# Power.net
KiCad netlist of a schematic drawn in Altium Designer
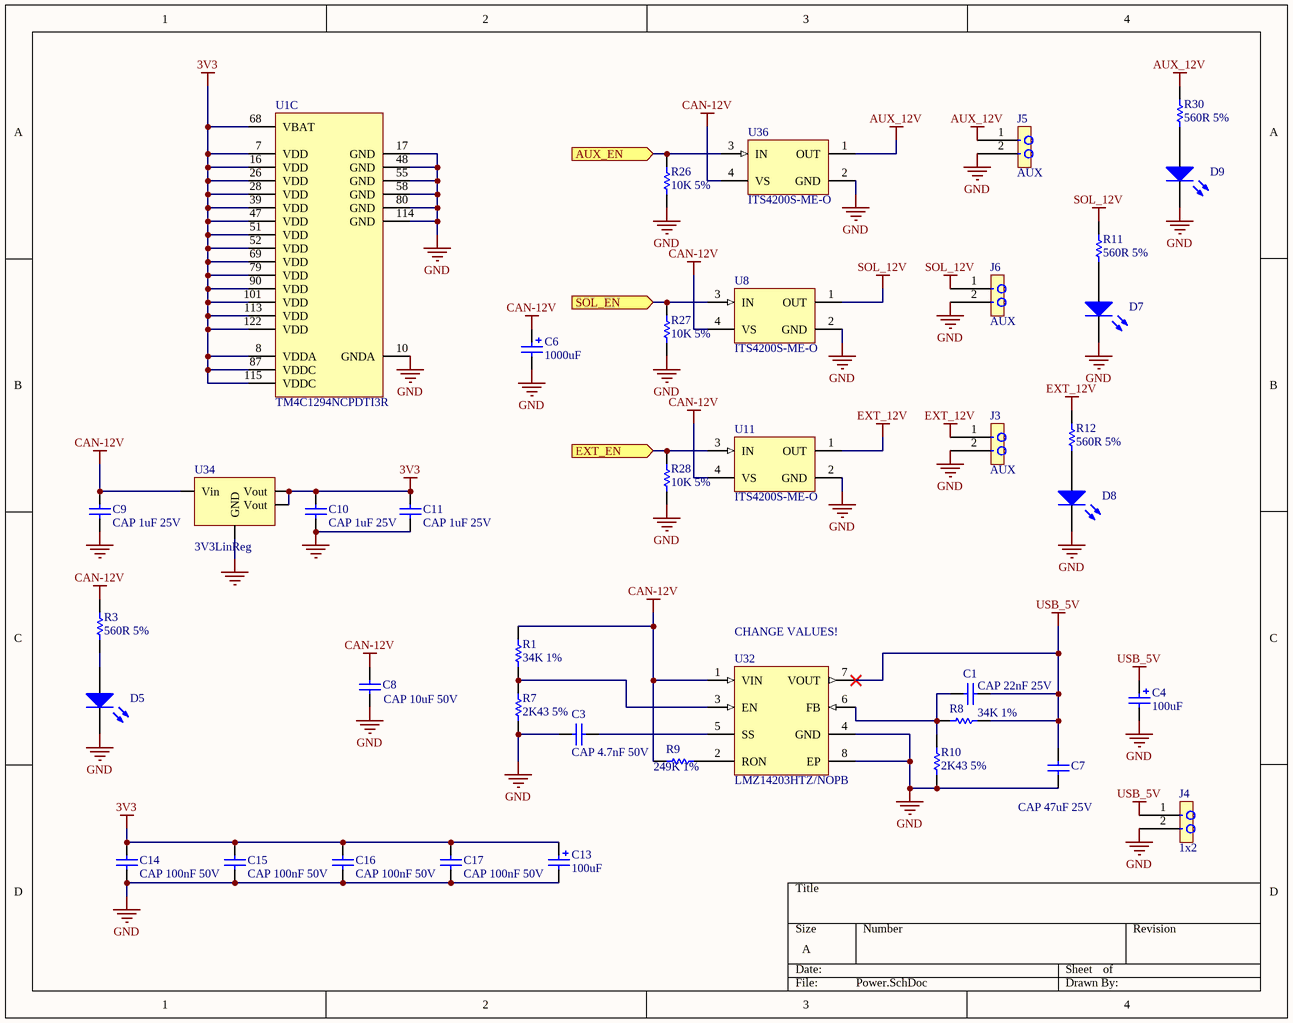
[diagram p0: Power.SchDoc]

(export (version "E")
  (design (tool "Eeschema 10.0.6"))
  (components
    (comp (ref "C1")
      (value "CAP 22nF 25V")
      (footprint "CAPC0805(2012)100_M")
      (description "CAP 22nF 25V Â±5% 0805 (2012 Metric) Thickness 1mm SMD")
      (fields (field (name "TOLERANCE") "Â±5%"))
      (libsource (lib "Altium Content Vault") (part "CMP-1036-04051-1"))
    )
    (comp (ref "C3")
      (value "CAP 4.7nF 50V")
      (footprint "CAPC0603(1608)100_M")
      (description "CAP 4.7nF 50V Â±20% 0603 (1608 Metric) Thickness 1mm SMD")
      (fields (field (name "TOLERANCE") "Â±20%"))
      (libsource (lib "Altium Content Vault") (part "CMP-1035-00333-1"))
    )
    (comp (ref "C4")
      (value "100uF")
      (footprint "PANASONIC_C")
      (description "Polarized Capacitor (Surface Mount)")
      (fields (field (name "PUBLISHER") "Altium Limited"))
      (libsource (lib "snarc+") (part "Cap_Polarized_100uF"))
    )
    (comp (ref "C6")
      (value "1000uF")
      (footprint "PANASONIC_H13")
      (description "Polarized Capacitor (Surface Mount)")
      (fields (field (name "PUBLISHER") "Altium Limited"))
      (libsource (lib "snarc+") (part "Cap_Polarized_1000uF"))
    )
    (comp (ref "C7")
      (value "CAP 47uF 25V")
      (footprint "CAPC1206(3216)100_L")
      (description "CAP 47uF 25V Â±0.25pF 1206 (3216 Metric) Thickness 1mm SMD")
      (fields (field (name "TOLERANCE") "Â±0.25pF"))
      (libsource (lib "Altium Content Vault") (part "CMP-1037-00376-1"))
    )
    (comp (ref "C8")
      (value "CAP 10uF 50V")
      (footprint "CAPC1206(3216)190_M")
      (description "CAP 10uF 50V Â±10% 1206 (3216 Metric) Thickness 1.9mm SMD")
      (fields (field (name "TOLERANCE") "Â±10%"))
      (libsource (lib "Altium Content Vault") (part "CMP-1037-04982-1"))
    )
    (comp (ref "C9")
      (value "CAP 1uF 25V")
      (footprint "CAPC0603(1608)100_M")
      (description "CAP 1uF 25V Â±0.25pF 0603 (1608 Metric) Thickness 1mm SMD")
      (fields (field (name "TOLERANCE") "Â±0.25pF"))
      (libsource (lib "Altium Content Vault") (part "CMP-1035-00037-1"))
    )
    (comp (ref "C10")
      (value "CAP 1uF 25V")
      (footprint "CAPC0603(1608)100_M")
      (description "CAP 1uF 25V Â±0.25pF 0603 (1608 Metric) Thickness 1mm SMD")
      (fields (field (name "TOLERANCE") "Â±0.25pF"))
      (libsource (lib "Altium Content Vault") (part "CMP-1035-00037-1"))
    )
    (comp (ref "C11")
      (value "CAP 1uF 25V")
      (footprint "CAPC0603(1608)100_M")
      (description "CAP 1uF 25V Â±0.25pF 0603 (1608 Metric) Thickness 1mm SMD")
      (fields (field (name "TOLERANCE") "Â±0.25pF"))
      (libsource (lib "Altium Content Vault") (part "CMP-1035-00037-1"))
    )
    (comp (ref "C13")
      (value "100uF")
      (footprint "PANASONIC_C")
      (description "Polarized Capacitor (Surface Mount)")
      (fields (field (name "PUBLISHER") "Altium Limited"))
      (libsource (lib "snarc+") (part "Cap_Polarized_100uF"))
    )
    (comp (ref "C14")
      (value "CAP 100nF 50V")
      (footprint "CAPC0603(1608)100_M")
      (description "CAP 100nF 50V Â±0.1pF 0603 (1608 Metric) Thickness 1mm SMD")
      (fields (field (name "TOLERANCE") "Â±0.1pF"))
      (libsource (lib "Altium Content Vault") (part "CMP-1035-00010-1"))
    )
    (comp (ref "C15")
      (value "CAP 100nF 50V")
      (footprint "CAPC0603(1608)100_M")
      (description "CAP 100nF 50V Â±0.1pF 0603 (1608 Metric) Thickness 1mm SMD")
      (fields (field (name "TOLERANCE") "Â±0.1pF"))
      (libsource (lib "Altium Content Vault") (part "CMP-1035-00010-1"))
    )
    (comp (ref "C16")
      (value "CAP 100nF 50V")
      (footprint "CAPC0603(1608)100_M")
      (description "CAP 100nF 50V Â±0.1pF 0603 (1608 Metric) Thickness 1mm SMD")
      (fields (field (name "TOLERANCE") "Â±0.1pF"))
      (libsource (lib "Altium Content Vault") (part "CMP-1035-00010-1"))
    )
    (comp (ref "C17")
      (value "CAP 100nF 50V")
      (footprint "CAPC0603(1608)100_M")
      (description "CAP 100nF 50V Â±0.1pF 0603 (1608 Metric) Thickness 1mm SMD")
      (fields (field (name "TOLERANCE") "Â±0.1pF"))
      (libsource (lib "Altium Content Vault") (part "CMP-1035-00010-1"))
    )
    (comp (ref "D5")
      (value "LED")
      (footprint "LED-0603")
      (description "Typical RED, GREEN, YELLOW, AMBER GaAs LED")
      (fields (field (name "PUBLISHER") "Altium Limited"))
      (libsource (lib "HSBNE-Vend") (part "LED"))
    )
    (comp (ref "D7")
      (value "LED")
      (footprint "LED-0603")
      (description "Typical RED, GREEN, YELLOW, AMBER GaAs LED")
      (fields (field (name "PUBLISHER") "Altium Limited"))
      (libsource (lib "HSBNE-Vend") (part "LED"))
    )
    (comp (ref "D8")
      (value "LED")
      (footprint "LED-0603")
      (description "Typical RED, GREEN, YELLOW, AMBER GaAs LED")
      (fields (field (name "PUBLISHER") "Altium Limited"))
      (libsource (lib "HSBNE-Vend") (part "LED"))
    )
    (comp (ref "D9")
      (value "LED")
      (footprint "LED-0603")
      (description "Typical RED, GREEN, YELLOW, AMBER GaAs LED")
      (fields (field (name "PUBLISHER") "Altium Limited"))
      (libsource (lib "HSBNE-Vend") (part "LED"))
    )
    (comp (ref "J3")
      (value "AUX")
      (footprint "M5569-2")
      (description "6.35mm right-angle 90° male spade terminal PCB mount")
      (libsource (lib "HSBNE-Vend") (part "CON2"))
    )
    (comp (ref "J4")
      (value "1x2")
      (footprint "1X2")
      (description "6.35mm right-angle 90° male spade terminal PCB mount")
      (libsource (lib "HSBNE-Vend") (part "CON2"))
    )
    (comp (ref "J5")
      (value "AUX")
      (footprint "M5569-2")
      (description "6.35mm right-angle 90° male spade terminal PCB mount")
      (libsource (lib "HSBNE-Vend") (part "CON2"))
    )
    (comp (ref "J6")
      (value "AUX")
      (footprint "M5569-2")
      (description "6.35mm right-angle 90° male spade terminal PCB mount")
      (libsource (lib "HSBNE-Vend") (part "CON2"))
    )
    (comp (ref "R1")
      (value "34K 1%")
      (footprint "RESC0603(1608)_M")
      (description "34K 0.1W 1% 0603 (1608 Metric)  SMD")
      (fields (field (name "TOLERANCE") "1 %") (field (name "POWER") "0.1 W"))
      (libsource (lib "Altium Content Vault") (part "CMP-1012-00682-1"))
    )
    (comp (ref "R3")
      (value "560R 5%")
      (footprint "RESC0603(1608)_M")
      (description "560R 0.1W 5% 0603 (1608 Metric)  SMD")
      (fields (field (name "TOLERANCE") "5 %") (field (name "POWER") "0.1 W"))
      (libsource (lib "Altium Content Vault") (part "RES"))
    )
    (comp (ref "R7")
      (value "2K43 5%")
      (footprint "RESC0603(1608)_M")
      (description "2K43 0.1W 5% 0603 (1608 Metric)  SMD")
      (fields (field (name "TOLERANCE") "5 %") (field (name "POWER") "0.1 W"))
      (libsource (lib "Altium Content Vault") (part "CMP-1012-00083-1"))
    )
    (comp (ref "R8")
      (value "34K 1%")
      (footprint "RESC0603(1608)_M")
      (description "34K 0.1W 1% 0603 (1608 Metric)  SMD")
      (fields (field (name "TOLERANCE") "1 %") (field (name "POWER") "0.1 W"))
      (libsource (lib "Altium Content Vault") (part "CMP-1012-00682-1"))
    )
    (comp (ref "R9")
      (value "249K 1%")
      (footprint "RESC0603(1608)_M")
      (description "249K 0.1W 1% 0603 (1608 Metric)  SMD")
      (fields (field (name "POWER") "0.1 W") (field (name "TOLERANCE") "1 %"))
      (libsource (lib "Altium Content Vault") (part "CMP-1012-00779-1"))
    )
    (comp (ref "R10")
      (value "2K43 5%")
      (footprint "RESC0603(1608)_M")
      (description "2K43 0.1W 5% 0603 (1608 Metric)  SMD")
      (fields (field (name "TOLERANCE") "5 %") (field (name "POWER") "0.1 W"))
      (libsource (lib "Altium Content Vault") (part "CMP-1012-00083-1"))
    )
    (comp (ref "R11")
      (value "560R 5%")
      (footprint "RESC0603(1608)_M")
      (description "560R 0.1W 5% 0603 (1608 Metric)  SMD")
      (fields (field (name "TOLERANCE") "5 %") (field (name "POWER") "0.1 W"))
      (libsource (lib "Altium Content Vault") (part "RES"))
    )
    (comp (ref "R12")
      (value "560R 5%")
      (footprint "RESC0603(1608)_M")
      (description "560R 0.1W 5% 0603 (1608 Metric)  SMD")
      (fields (field (name "TOLERANCE") "5 %") (field (name "POWER") "0.1 W"))
      (libsource (lib "Altium Content Vault") (part "RES"))
    )
    (comp (ref "R26")
      (value "10K 5%")
      (footprint "RESC0603(1608)_N")
      (description "10K 0.1W 5% 0603 (1608 Metric)  SMD")
      (fields (field (name "TOLERANCE") "5 %") (field (name "POWER") "0.1 W"))
      (libsource (lib "Altium Content Vault") (part "RES"))
    )
    (comp (ref "R27")
      (value "10K 5%")
      (footprint "RESC0603(1608)_N")
      (description "10K 0.1W 5% 0603 (1608 Metric)  SMD")
      (fields (field (name "TOLERANCE") "5 %") (field (name "POWER") "0.1 W"))
      (libsource (lib "Altium Content Vault") (part "RES"))
    )
    (comp (ref "R28")
      (value "10K 5%")
      (footprint "RESC0603(1608)_N")
      (description "10K 0.1W 5% 0603 (1608 Metric)  SMD")
      (fields (field (name "TOLERANCE") "5 %") (field (name "POWER") "0.1 W"))
      (libsource (lib "Altium Content Vault") (part "RES"))
    )
    (comp (ref "R30")
      (value "560R 5%")
      (footprint "RESC0603(1608)_M")
      (description "560R 0.1W 5% 0603 (1608 Metric)  SMD")
      (fields (field (name "TOLERANCE") "5 %") (field (name "POWER") "0.1 W"))
      (libsource (lib "Altium Content Vault") (part "RES"))
    )
    (comp (ref "U1")
      (value "TM4C1294NCPDTI3R")
      (footprint "TI-PDT128_M")
      (fields (field (name "MANUFACTURER") "Texas Instruments"))
      (libsource (lib "Altium Inc") (part "TI-TM4C1294NCPDT-128"))
    )
    (comp (ref "U8")
      (value "ITS4200S-ME-O")
      (footprint "INF-SOT223_M")
      (description "Smart High-Side NMOS-Power Switch, 11 to 45 V Operating, -40 to 125 degC, SOT223, Reel, Green")
      (fields (field (name "MANUFACTURER") "Infineon"))
      (libsource (lib "Altium Content Vault") (part "INF-ITS4200S-ME-X-SOT223-4"))
    )
    (comp (ref "U11")
      (value "ITS4200S-ME-O")
      (footprint "INF-SOT223_M")
      (description "Smart High-Side NMOS-Power Switch, 11 to 45 V Operating, -40 to 125 degC, SOT223, Reel, Green")
      (fields (field (name "MANUFACTURER") "Infineon"))
      (libsource (lib "Altium Content Vault") (part "INF-ITS4200S-ME-X-SOT223-4"))
    )
    (comp (ref "U32")
      (value "LMZ14203HTZ/NOPB")
      (footprint "TZA07A_V")
      (fields (field (name "MANUFACTURER") "National Semiconductor"))
      (libsource (lib "Altium Content Vault") (part "PM-REG-LMZ12003-8"))
    )
    (comp (ref "U34")
      (value "3V3LinReg")
      (footprint "SOT-223")
      (description "Reg 1A 3V3 OUT SIP VERT")
      (libsource (lib "HSBNE-Vend") (part "AZ1117EH"))
    )
    (comp (ref "U36")
      (value "ITS4200S-ME-O")
      (footprint "INF-SOT223_M")
      (description "Smart High-Side NMOS-Power Switch, 11 to 45 V Operating, -40 to 125 degC, SOT223, Reel, Green")
      (fields (field (name "MANUFACTURER") "Infineon"))
      (libsource (lib "Altium Content Vault") (part "INF-ITS4200S-ME-X-SOT223-4"))
    )
  )
  (nets
    (net (code "1") (name "/AUX_EN") (class "Default")
      (node (ref "R26") (pin "2") (pinfunction "2_2") (pintype "passive"))
      (node (ref "U36") (pin "3") (pinfunction "IN_3") (pintype "input"))
    )
    (net (code "2") (name "/EXT_EN") (class "Default")
      (node (ref "R28") (pin "2") (pinfunction "2_2") (pintype "passive"))
      (node (ref "U11") (pin "3") (pinfunction "IN_3") (pintype "input"))
    )
    (net (code "3") (name "/SOL_EN") (class "Default")
      (node (ref "R27") (pin "2") (pinfunction "2_2") (pintype "passive"))
      (node (ref "U8") (pin "3") (pinfunction "IN_3") (pintype "input"))
    )
    (net (code "4") (name "3V3") (class "Default")
      (node (ref "C10") (pin "2") (pinfunction "2_2") (pintype "passive"))
      (node (ref "C11") (pin "2") (pinfunction "2_2") (pintype "passive"))
      (node (ref "C13") (pin "+") (pinfunction "+_+") (pintype "passive"))
      (node (ref "C14") (pin "2") (pinfunction "2_2") (pintype "passive"))
      (node (ref "C15") (pin "2") (pinfunction "2_2") (pintype "passive"))
      (node (ref "C16") (pin "2") (pinfunction "2_2") (pintype "passive"))
      (node (ref "C17") (pin "2") (pinfunction "2_2") (pintype "passive"))
      (node (ref "U1") (pin "101") (pinfunction "VDD_101") (pintype "power_in"))
      (node (ref "U1") (pin "113") (pinfunction "VDD_113") (pintype "power_in"))
      (node (ref "U1") (pin "115") (pinfunction "VDDC_115") (pintype "power_in"))
      (node (ref "U1") (pin "122") (pinfunction "VDD_122") (pintype "power_in"))
      (node (ref "U1") (pin "16") (pinfunction "VDD_16") (pintype "power_in"))
      (node (ref "U1") (pin "26") (pinfunction "VDD_26") (pintype "power_in"))
      (node (ref "U1") (pin "28") (pinfunction "VDD_28") (pintype "power_in"))
      (node (ref "U1") (pin "39") (pinfunction "VDD_39") (pintype "power_in"))
      (node (ref "U1") (pin "47") (pinfunction "VDD_47") (pintype "power_in"))
      (node (ref "U1") (pin "51") (pinfunction "VDD_51") (pintype "power_in"))
      (node (ref "U1") (pin "52") (pinfunction "VDD_52") (pintype "power_in"))
      (node (ref "U1") (pin "68") (pinfunction "VBAT_68") (pintype "power_in"))
      (node (ref "U1") (pin "69") (pinfunction "VDD_69") (pintype "power_in"))
      (node (ref "U1") (pin "7") (pinfunction "VDD_7") (pintype "power_in"))
      (node (ref "U1") (pin "79") (pinfunction "VDD_79") (pintype "power_in"))
      (node (ref "U1") (pin "8") (pinfunction "VDDA_8") (pintype "power_in"))
      (node (ref "U1") (pin "87") (pinfunction "VDDC_87") (pintype "power_in"))
      (node (ref "U1") (pin "90") (pinfunction "VDD_90") (pintype "power_in"))
      (node (ref "U34") (pin "2") (pinfunction "Vout_2") (pintype "power_in"))
      (node (ref "U34") (pin "4") (pinfunction "Vout_4") (pintype "power_in"))
    )
    (net (code "5") (name "AUX_12V") (class "Default")
      (node (ref "J5") (pin "1") (pintype "passive"))
      (node (ref "R30") (pin "2") (pinfunction "2_2") (pintype "passive"))
      (node (ref "U36") (pin "1") (pinfunction "OUT_1") (pintype "power_in"))
    )
    (net (code "6") (name "CAN-12V") (class "Default")
      (node (ref "C6") (pin "+") (pinfunction "+_+") (pintype "passive"))
      (node (ref "C8") (pin "1") (pinfunction "1_1") (pintype "passive"))
      (node (ref "C9") (pin "2") (pinfunction "2_2") (pintype "passive"))
      (node (ref "R1") (pin "2") (pinfunction "2_2") (pintype "passive"))
      (node (ref "R3") (pin "2") (pinfunction "2_2") (pintype "passive"))
      (node (ref "R9") (pin "1") (pinfunction "1_1") (pintype "passive"))
      (node (ref "U11") (pin "4") (pinfunction "VS_4") (pintype "power_in"))
      (node (ref "U32") (pin "1") (pinfunction "VIN_1") (pintype "input"))
      (node (ref "U34") (pin "3") (pinfunction "Vin_3") (pintype "power_in"))
      (node (ref "U36") (pin "4") (pinfunction "VS_4") (pintype "power_in"))
      (node (ref "U8") (pin "4") (pinfunction "VS_4") (pintype "power_in"))
    )
    (net (code "7") (name "EXT_12V") (class "Default")
      (node (ref "J3") (pin "1") (pintype "passive"))
      (node (ref "R12") (pin "2") (pinfunction "2_2") (pintype "passive"))
      (node (ref "U11") (pin "1") (pinfunction "OUT_1") (pintype "power_in"))
    )
    (net (code "8") (name "GND") (class "Default")
      (node (ref "C10") (pin "1") (pinfunction "1_1") (pintype "passive"))
      (node (ref "C11") (pin "1") (pinfunction "1_1") (pintype "passive"))
      (node (ref "C13") (pin "-") (pinfunction "-_-") (pintype "passive"))
      (node (ref "C14") (pin "1") (pinfunction "1_1") (pintype "passive"))
      (node (ref "C15") (pin "1") (pinfunction "1_1") (pintype "passive"))
      (node (ref "C16") (pin "1") (pinfunction "1_1") (pintype "passive"))
      (node (ref "C17") (pin "1") (pinfunction "1_1") (pintype "passive"))
      (node (ref "C3") (pin "1") (pinfunction "1_1") (pintype "passive"))
      (node (ref "C4") (pin "-") (pinfunction "-_-") (pintype "passive"))
      (node (ref "C6") (pin "-") (pinfunction "-_-") (pintype "passive"))
      (node (ref "C7") (pin "2") (pinfunction "2_2") (pintype "passive"))
      (node (ref "C8") (pin "2") (pinfunction "2_2") (pintype "passive"))
      (node (ref "C9") (pin "1") (pinfunction "1_1") (pintype "passive"))
      (node (ref "D5") (pin "2") (pinfunction "K_2") (pintype "passive"))
      (node (ref "D7") (pin "2") (pinfunction "K_2") (pintype "passive"))
      (node (ref "D8") (pin "2") (pinfunction "K_2") (pintype "passive"))
      (node (ref "D9") (pin "2") (pinfunction "K_2") (pintype "passive"))
      (node (ref "J3") (pin "2") (pintype "passive"))
      (node (ref "J4") (pin "2") (pintype "passive"))
      (node (ref "J5") (pin "2") (pintype "passive"))
      (node (ref "J6") (pin "2") (pintype "passive"))
      (node (ref "R10") (pin "1") (pinfunction "1_1") (pintype "passive"))
      (node (ref "R26") (pin "1") (pinfunction "1_1") (pintype "passive"))
      (node (ref "R27") (pin "1") (pinfunction "1_1") (pintype "passive"))
      (node (ref "R28") (pin "1") (pinfunction "1_1") (pintype "passive"))
      (node (ref "R7") (pin "1") (pinfunction "1_1") (pintype "passive"))
      (node (ref "U1") (pin "10") (pinfunction "GNDA_10") (pintype "power_in"))
      (node (ref "U1") (pin "114") (pinfunction "GND_114") (pintype "power_in"))
      (node (ref "U1") (pin "17") (pinfunction "GND_17") (pintype "power_in"))
      (node (ref "U1") (pin "48") (pinfunction "GND_48") (pintype "power_in"))
      (node (ref "U1") (pin "55") (pinfunction "GND_55") (pintype "power_in"))
      (node (ref "U1") (pin "58") (pinfunction "GND_58") (pintype "power_in"))
      (node (ref "U1") (pin "80") (pinfunction "GND_80") (pintype "power_in"))
      (node (ref "U11") (pin "2") (pinfunction "GND_2") (pintype "power_in"))
      (node (ref "U32") (pin "4") (pinfunction "GND_4") (pintype "power_in"))
      (node (ref "U32") (pin "8") (pinfunction "EP_8") (pintype "passive"))
      (node (ref "U34") (pin "1") (pinfunction "GND_1") (pintype "power_in"))
      (node (ref "U36") (pin "2") (pinfunction "GND_2") (pintype "power_in"))
      (node (ref "U8") (pin "2") (pinfunction "GND_2") (pintype "power_in"))
    )
    (net (code "9") (name "Net-(D5-A)") (class "Default")
      (node (ref "D5") (pin "1") (pinfunction "A_1") (pintype "passive"))
      (node (ref "R3") (pin "1") (pinfunction "1_1") (pintype "passive"))
    )
    (net (code "10") (name "Net-(D7-A)") (class "Default")
      (node (ref "D7") (pin "1") (pinfunction "A_1") (pintype "passive"))
      (node (ref "R11") (pin "1") (pinfunction "1_1") (pintype "passive"))
    )
    (net (code "11") (name "Net-(D8-A)") (class "Default")
      (node (ref "D8") (pin "1") (pinfunction "A_1") (pintype "passive"))
      (node (ref "R12") (pin "1") (pinfunction "1_1") (pintype "passive"))
    )
    (net (code "12") (name "Net-(D9-A)") (class "Default")
      (node (ref "D9") (pin "1") (pinfunction "A_1") (pintype "passive"))
      (node (ref "R30") (pin "1") (pinfunction "1_1") (pintype "passive"))
    )
    (net (code "13") (name "Net-(U32-EN)") (class "Default")
      (node (ref "R1") (pin "1") (pinfunction "1_1") (pintype "passive"))
      (node (ref "R7") (pin "2") (pinfunction "2_2") (pintype "passive"))
      (node (ref "U32") (pin "3") (pinfunction "EN_3") (pintype "input"))
    )
    (net (code "14") (name "Net-(U32-FB)") (class "Default")
      (node (ref "C1") (pin "1") (pinfunction "1_1") (pintype "passive"))
      (node (ref "R10") (pin "2") (pinfunction "2_2") (pintype "passive"))
      (node (ref "R8") (pin "1") (pinfunction "1_1") (pintype "passive"))
      (node (ref "U32") (pin "6") (pinfunction "FB_6") (pintype "input"))
    )
    (net (code "15") (name "Net-(U32-RON)") (class "Default")
      (node (ref "R9") (pin "2") (pinfunction "2_2") (pintype "passive"))
      (node (ref "U32") (pin "2") (pinfunction "RON_2") (pintype "passive"))
    )
    (net (code "16") (name "Net-(U32-SS)") (class "Default")
      (node (ref "C3") (pin "2") (pinfunction "2_2") (pintype "passive"))
      (node (ref "U32") (pin "5") (pinfunction "SS_5") (pintype "passive"))
    )
    (net (code "17") (name "SOL_12V") (class "Default")
      (node (ref "J6") (pin "1") (pintype "passive"))
      (node (ref "R11") (pin "2") (pinfunction "2_2") (pintype "passive"))
      (node (ref "U8") (pin "1") (pinfunction "OUT_1") (pintype "power_in"))
    )
    (net (code "18") (name "USB_5V") (class "Default")
      (node (ref "C1") (pin "2") (pinfunction "2_2") (pintype "passive"))
      (node (ref "C4") (pin "+") (pinfunction "+_+") (pintype "passive"))
      (node (ref "C7") (pin "1") (pinfunction "1_1") (pintype "passive"))
      (node (ref "J4") (pin "1") (pintype "passive"))
      (node (ref "R8") (pin "2") (pinfunction "2_2") (pintype "passive"))
      (node (ref "U32") (pin "7") (pinfunction "VOUT_7") (pintype "output"))
    )
  )
)
